# 04_LCD.net
KiCad netlist of a schematic drawn in Altium Designer
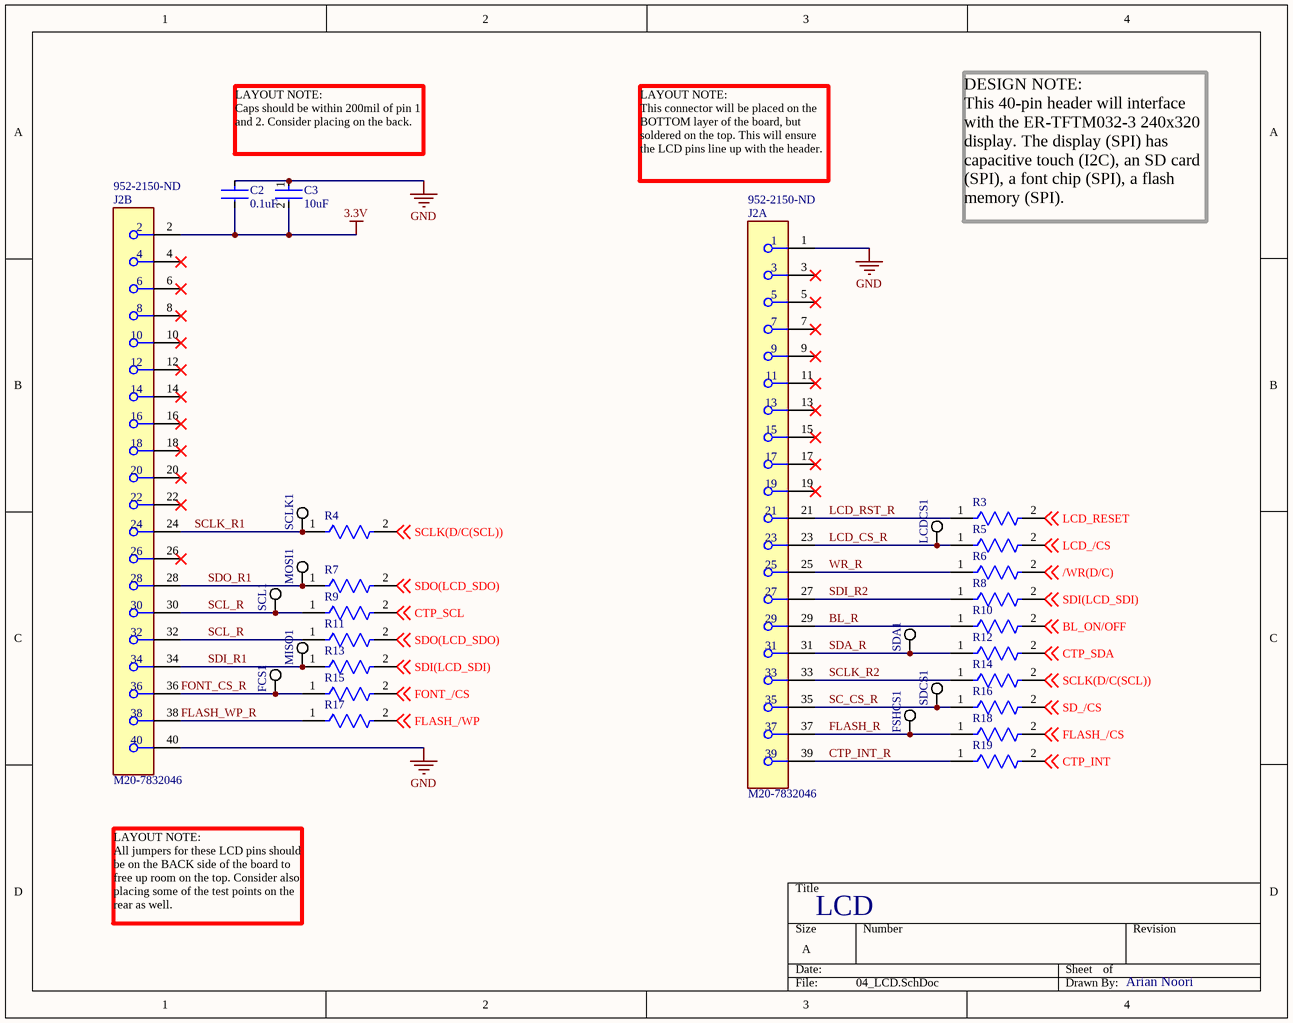
[diagram p0: 04_LCD.SchDoc]

(export (version "E")
  (design (tool "Eeschema 10.0.6"))
  (components
    (comp (ref "C2")
      (value "0.1uF")
      (footprint "FP-CL21-IPC_C")
      (description "CL21 Series 0805 100nF 50V ±10% Tolerance X7R Multilayer Ceramic Chip Capacitor")
      (fields (field (name "TOLERANCE") "10%") (field (name "VOLTAGE") "50V"))
      (libsource (lib "Altium Content Vault") (part "b4654b650e69147ec39a6b967a45e02"))
    )
    (comp (ref "C3")
      (value "10uF")
      (footprint "FP-C0805C-DG-MFG")
      (description "CAP CER 10UF 10V X5R 0805")
      (fields (field (name "TOLERANCE") "10%") (field (name "MANUFACTURER PART NUMBER") "C0805C106K8PACTU"))
      (libsource (lib "Altium Content Vault") (part "11868f565c42a9108669ba33697ecf6"))
    )
    (comp (ref "FCS1")
      (value "5019")
      (footprint "KSTN-5019_V")
      (description "Test Point, 1 Position SMD, RoHS, Tape and Reel")
      (fields (field (name "MANUFACTURER") "Keystone Electronics"))
      (libsource (lib "Altium Content Vault") (part "TESTPOINT_WHITE"))
    )
    (comp (ref "FSHCS1")
      (value "5019")
      (footprint "KSTN-5019_V")
      (description "Test Point, 1 Position SMD, RoHS, Tape and Reel")
      (fields (field (name "MANUFACTURER") "Keystone Electronics"))
      (libsource (lib "Altium Content Vault") (part "TESTPOINT_WHITE"))
    )
    (comp (ref "J2")
      (value "M20-7832046")
      (footprint "FP-M20-7832046-MFG")
      (description "CONN RCPT 40POS 0.1 TIN PCB")
      (fields (field (name "SUPPLIER PART NUMBER 1") "952-2150-ND") (field (name "MANUFACTURER") "Harwin"))
      (libsource (lib "Altium Content Vault") (part "e49c40d8a4b72700ef4f9e86232dadc"))
    )
    (comp (ref "LCDCS1")
      (value "5019")
      (footprint "KSTN-5019_V")
      (description "Test Point, 1 Position SMD, RoHS, Tape and Reel")
      (fields (field (name "MANUFACTURER") "Keystone Electronics"))
      (libsource (lib "Altium Content Vault") (part "TESTPOINT_WHITE"))
    )
    (comp (ref "MISO1")
      (value "5019")
      (footprint "KSTN-5019_V")
      (description "Test Point, 1 Position SMD, RoHS, Tape and Reel")
      (fields (field (name "MANUFACTURER") "Keystone Electronics"))
      (libsource (lib "Altium Content Vault") (part "TESTPOINT_WHITE"))
    )
    (comp (ref "MOSI1")
      (value "5019")
      (footprint "KSTN-5019_V")
      (description "Test Point, 1 Position SMD, RoHS, Tape and Reel")
      (fields (field (name "MANUFACTURER") "Keystone Electronics"))
      (libsource (lib "Altium Content Vault") (part "TESTPOINT_WHITE"))
    )
    (comp (ref "R3")
      (value "~")
      (footprint "FP-RC0805-MFG")
      (description "RES SMD 0 OHM JUMPER 1/8W 0805")
      (fields
        (field (name "OCTOPART") "https://octopart.com/rc0805fr-070rl-yageo-9293404")
        (field (name "MANUFACTURER") "Yageo")
      )
      (libsource (lib "Altium Content Vault") (part "1029c3af85768c4190bb7ad29bc67b5"))
    )
    (comp (ref "R4")
      (value "~")
      (footprint "FP-RC0805-MFG")
      (description "RES SMD 0 OHM JUMPER 1/8W 0805")
      (fields
        (field (name "OCTOPART") "https://octopart.com/rc0805fr-070rl-yageo-9293404")
        (field (name "MANUFACTURER") "Yageo")
      )
      (libsource (lib "Altium Content Vault") (part "1029c3af85768c4190bb7ad29bc67b5"))
    )
    (comp (ref "R5")
      (value "~")
      (footprint "FP-RC0805-MFG")
      (description "RES SMD 0 OHM JUMPER 1/8W 0805")
      (fields
        (field (name "OCTOPART") "https://octopart.com/rc0805fr-070rl-yageo-9293404")
        (field (name "MANUFACTURER") "Yageo")
      )
      (libsource (lib "Altium Content Vault") (part "1029c3af85768c4190bb7ad29bc67b5"))
    )
    (comp (ref "R6")
      (value "~")
      (footprint "FP-RC0805-MFG")
      (description "RES SMD 0 OHM JUMPER 1/8W 0805")
      (fields
        (field (name "OCTOPART") "https://octopart.com/rc0805fr-070rl-yageo-9293404")
        (field (name "MANUFACTURER") "Yageo")
      )
      (libsource (lib "Altium Content Vault") (part "1029c3af85768c4190bb7ad29bc67b5"))
    )
    (comp (ref "R7")
      (value "~")
      (footprint "FP-RC0805-MFG")
      (description "RES SMD 0 OHM JUMPER 1/8W 0805")
      (fields
        (field (name "OCTOPART") "https://octopart.com/rc0805fr-070rl-yageo-9293404")
        (field (name "MANUFACTURER") "Yageo")
      )
      (libsource (lib "Altium Content Vault") (part "1029c3af85768c4190bb7ad29bc67b5"))
    )
    (comp (ref "R8")
      (value "~")
      (footprint "FP-RC0805-MFG")
      (description "RES SMD 0 OHM JUMPER 1/8W 0805")
      (fields
        (field (name "OCTOPART") "https://octopart.com/rc0805fr-070rl-yageo-9293404")
        (field (name "MANUFACTURER") "Yageo")
      )
      (libsource (lib "Altium Content Vault") (part "1029c3af85768c4190bb7ad29bc67b5"))
    )
    (comp (ref "R9")
      (value "~")
      (footprint "FP-RC0805-MFG")
      (description "RES SMD 0 OHM JUMPER 1/8W 0805")
      (fields
        (field (name "OCTOPART") "https://octopart.com/rc0805fr-070rl-yageo-9293404")
        (field (name "MANUFACTURER") "Yageo")
      )
      (libsource (lib "Altium Content Vault") (part "1029c3af85768c4190bb7ad29bc67b5"))
    )
    (comp (ref "R10")
      (value "~")
      (footprint "FP-RC0805-MFG")
      (description "RES SMD 0 OHM JUMPER 1/8W 0805")
      (fields
        (field (name "OCTOPART") "https://octopart.com/rc0805fr-070rl-yageo-9293404")
        (field (name "MANUFACTURER") "Yageo")
      )
      (libsource (lib "Altium Content Vault") (part "1029c3af85768c4190bb7ad29bc67b5"))
    )
    (comp (ref "R11")
      (value "~")
      (footprint "FP-RC0805-MFG")
      (description "RES SMD 0 OHM JUMPER 1/8W 0805")
      (fields
        (field (name "OCTOPART") "https://octopart.com/rc0805fr-070rl-yageo-9293404")
        (field (name "MANUFACTURER") "Yageo")
      )
      (libsource (lib "Altium Content Vault") (part "1029c3af85768c4190bb7ad29bc67b5"))
    )
    (comp (ref "R12")
      (value "~")
      (footprint "FP-RC0805-MFG")
      (description "RES SMD 0 OHM JUMPER 1/8W 0805")
      (fields
        (field (name "OCTOPART") "https://octopart.com/rc0805fr-070rl-yageo-9293404")
        (field (name "MANUFACTURER") "Yageo")
      )
      (libsource (lib "Altium Content Vault") (part "1029c3af85768c4190bb7ad29bc67b5"))
    )
    (comp (ref "R13")
      (value "~")
      (footprint "FP-RC0805-MFG")
      (description "RES SMD 0 OHM JUMPER 1/8W 0805")
      (fields
        (field (name "OCTOPART") "https://octopart.com/rc0805fr-070rl-yageo-9293404")
        (field (name "MANUFACTURER") "Yageo")
      )
      (libsource (lib "Altium Content Vault") (part "1029c3af85768c4190bb7ad29bc67b5"))
    )
    (comp (ref "R14")
      (value "~")
      (footprint "FP-RC0805-MFG")
      (description "RES SMD 0 OHM JUMPER 1/8W 0805")
      (fields
        (field (name "OCTOPART") "https://octopart.com/rc0805fr-070rl-yageo-9293404")
        (field (name "MANUFACTURER") "Yageo")
      )
      (libsource (lib "Altium Content Vault") (part "1029c3af85768c4190bb7ad29bc67b5"))
    )
    (comp (ref "R15")
      (value "~")
      (footprint "FP-RC0805-MFG")
      (description "RES SMD 0 OHM JUMPER 1/8W 0805")
      (fields
        (field (name "OCTOPART") "https://octopart.com/rc0805fr-070rl-yageo-9293404")
        (field (name "MANUFACTURER") "Yageo")
      )
      (libsource (lib "Altium Content Vault") (part "1029c3af85768c4190bb7ad29bc67b5"))
    )
    (comp (ref "R16")
      (value "~")
      (footprint "FP-RC0805-MFG")
      (description "RES SMD 0 OHM JUMPER 1/8W 0805")
      (fields
        (field (name "OCTOPART") "https://octopart.com/rc0805fr-070rl-yageo-9293404")
        (field (name "MANUFACTURER") "Yageo")
      )
      (libsource (lib "Altium Content Vault") (part "1029c3af85768c4190bb7ad29bc67b5"))
    )
    (comp (ref "R17")
      (value "~")
      (footprint "FP-RC0805-MFG")
      (description "RES SMD 0 OHM JUMPER 1/8W 0805")
      (fields
        (field (name "OCTOPART") "https://octopart.com/rc0805fr-070rl-yageo-9293404")
        (field (name "MANUFACTURER") "Yageo")
      )
      (libsource (lib "Altium Content Vault") (part "1029c3af85768c4190bb7ad29bc67b5"))
    )
    (comp (ref "R18")
      (value "~")
      (footprint "FP-RC0805-MFG")
      (description "RES SMD 0 OHM JUMPER 1/8W 0805")
      (fields
        (field (name "OCTOPART") "https://octopart.com/rc0805fr-070rl-yageo-9293404")
        (field (name "MANUFACTURER") "Yageo")
      )
      (libsource (lib "Altium Content Vault") (part "1029c3af85768c4190bb7ad29bc67b5"))
    )
    (comp (ref "R19")
      (value "~")
      (footprint "FP-RC0805-MFG")
      (description "RES SMD 0 OHM JUMPER 1/8W 0805")
      (fields
        (field (name "OCTOPART") "https://octopart.com/rc0805fr-070rl-yageo-9293404")
        (field (name "MANUFACTURER") "Yageo")
      )
      (libsource (lib "Altium Content Vault") (part "1029c3af85768c4190bb7ad29bc67b5"))
    )
    (comp (ref "SCL1")
      (value "5019")
      (footprint "KSTN-5019_V")
      (description "Test Point, 1 Position SMD, RoHS, Tape and Reel")
      (fields (field (name "MANUFACTURER") "Keystone Electronics"))
      (libsource (lib "Altium Content Vault") (part "TESTPOINT_WHITE"))
    )
    (comp (ref "SCLK1")
      (value "5019")
      (footprint "KSTN-5019_V")
      (description "Test Point, 1 Position SMD, RoHS, Tape and Reel")
      (fields (field (name "MANUFACTURER") "Keystone Electronics"))
      (libsource (lib "Altium Content Vault") (part "TESTPOINT_WHITE"))
    )
    (comp (ref "SDA1")
      (value "5019")
      (footprint "KSTN-5019_V")
      (description "Test Point, 1 Position SMD, RoHS, Tape and Reel")
      (fields (field (name "MANUFACTURER") "Keystone Electronics"))
      (libsource (lib "Altium Content Vault") (part "TESTPOINT_WHITE"))
    )
    (comp (ref "SDCS1")
      (value "5019")
      (footprint "KSTN-5019_V")
      (description "Test Point, 1 Position SMD, RoHS, Tape and Reel")
      (fields (field (name "MANUFACTURER") "Keystone Electronics"))
      (libsource (lib "Altium Content Vault") (part "TESTPOINT_WHITE"))
    )
  )
  (nets
    (net (code "1") (name "/BL_R") (class "Default")
      (node (ref "J2") (pin "29") (pinfunction "29_29") (pintype "passive"))
      (node (ref "R10") (pin "1") (pinfunction "1_1") (pintype "passive"))
    )
    (net (code "2") (name "/CTP_INT_R") (class "Default")
      (node (ref "J2") (pin "39") (pinfunction "39_39") (pintype "passive"))
      (node (ref "R19") (pin "1") (pinfunction "1_1") (pintype "passive"))
    )
    (net (code "3") (name "/FLASH_R") (class "Default")
      (node (ref "FSHCS1") (pin "1") (pinfunction "1_1") (pintype "passive"))
      (node (ref "J2") (pin "37") (pinfunction "37_37") (pintype "passive"))
      (node (ref "R18") (pin "1") (pinfunction "1_1") (pintype "passive"))
    )
    (net (code "4") (name "/FLASH_WP_R") (class "Default")
      (node (ref "J2") (pin "38") (pinfunction "38_38") (pintype "passive"))
      (node (ref "R17") (pin "1") (pinfunction "1_1") (pintype "passive"))
    )
    (net (code "5") (name "/FONT_CS_R") (class "Default")
      (node (ref "FCS1") (pin "1") (pinfunction "1_1") (pintype "passive"))
      (node (ref "J2") (pin "36") (pinfunction "36_36") (pintype "passive"))
      (node (ref "R15") (pin "1") (pinfunction "1_1") (pintype "passive"))
    )
    (net (code "6") (name "/LCD_CS_R") (class "Default")
      (node (ref "J2") (pin "23") (pinfunction "23_23") (pintype "passive"))
      (node (ref "LCDCS1") (pin "1") (pinfunction "1_1") (pintype "passive"))
      (node (ref "R5") (pin "1") (pinfunction "1_1") (pintype "passive"))
    )
    (net (code "7") (name "/LCD_RST_R") (class "Default")
      (node (ref "J2") (pin "21") (pinfunction "21_21") (pintype "passive"))
      (node (ref "R3") (pin "1") (pinfunction "1_1") (pintype "passive"))
    )
    (net (code "8") (name "/SCLK_R1") (class "Default")
      (node (ref "J2") (pin "24") (pinfunction "24_24") (pintype "passive"))
      (node (ref "R4") (pin "1") (pinfunction "1_1") (pintype "passive"))
      (node (ref "SCLK1") (pin "1") (pinfunction "1_1") (pintype "passive"))
    )
    (net (code "9") (name "/SCLK_R2") (class "Default")
      (node (ref "J2") (pin "33") (pinfunction "33_33") (pintype "passive"))
      (node (ref "R14") (pin "1") (pinfunction "1_1") (pintype "passive"))
    )
    (net (code "10") (name "/SCL_R") (class "Default")
      (node (ref "J2") (pin "30") (pinfunction "30_30") (pintype "passive"))
      (node (ref "J2") (pin "32") (pinfunction "32_32") (pintype "passive"))
      (node (ref "R11") (pin "1") (pinfunction "1_1") (pintype "passive"))
      (node (ref "R9") (pin "1") (pinfunction "1_1") (pintype "passive"))
      (node (ref "SCL1") (pin "1") (pinfunction "1_1") (pintype "passive"))
    )
    (net (code "11") (name "/SC_CS_R") (class "Default")
      (node (ref "J2") (pin "35") (pinfunction "35_35") (pintype "passive"))
      (node (ref "R16") (pin "1") (pinfunction "1_1") (pintype "passive"))
      (node (ref "SDCS1") (pin "1") (pinfunction "1_1") (pintype "passive"))
    )
    (net (code "12") (name "/SDA_R") (class "Default")
      (node (ref "J2") (pin "31") (pinfunction "31_31") (pintype "passive"))
      (node (ref "R12") (pin "1") (pinfunction "1_1") (pintype "passive"))
      (node (ref "SDA1") (pin "1") (pinfunction "1_1") (pintype "passive"))
    )
    (net (code "13") (name "/SDI_R1") (class "Default")
      (node (ref "J2") (pin "34") (pinfunction "34_34") (pintype "passive"))
      (node (ref "MISO1") (pin "1") (pinfunction "1_1") (pintype "passive"))
      (node (ref "R13") (pin "1") (pinfunction "1_1") (pintype "passive"))
    )
    (net (code "14") (name "/SDI_R2") (class "Default")
      (node (ref "J2") (pin "27") (pinfunction "27_27") (pintype "passive"))
      (node (ref "R8") (pin "1") (pinfunction "1_1") (pintype "passive"))
    )
    (net (code "15") (name "/SDO_R1") (class "Default")
      (node (ref "J2") (pin "28") (pinfunction "28_28") (pintype "passive"))
      (node (ref "MOSI1") (pin "1") (pinfunction "1_1") (pintype "passive"))
      (node (ref "R7") (pin "1") (pinfunction "1_1") (pintype "passive"))
    )
    (net (code "16") (name "/WR_R") (class "Default")
      (node (ref "J2") (pin "25") (pinfunction "25_25") (pintype "passive"))
      (node (ref "R6") (pin "1") (pinfunction "1_1") (pintype "passive"))
    )
    (net (code "17") (name "3.3V") (class "Default")
      (node (ref "C2") (pin "2") (pinfunction "2_2") (pintype "passive"))
      (node (ref "C3") (pin "2") (pinfunction "2_2") (pintype "passive"))
      (node (ref "J2") (pin "2") (pinfunction "2_2") (pintype "passive"))
    )
    (net (code "18") (name "BL_ON{slash}OFF") (class "Default")
      (node (ref "R10") (pin "2") (pinfunction "2_2") (pintype "passive"))
    )
    (net (code "19") (name "CTP_INT") (class "Default")
      (node (ref "R19") (pin "2") (pinfunction "2_2") (pintype "passive"))
    )
    (net (code "20") (name "CTP_SCL") (class "Default")
      (node (ref "R9") (pin "2") (pinfunction "2_2") (pintype "passive"))
    )
    (net (code "21") (name "CTP_SDA") (class "Default")
      (node (ref "R12") (pin "2") (pinfunction "2_2") (pintype "passive"))
    )
    (net (code "22") (name "FLASH_{slash}CS") (class "Default")
      (node (ref "R18") (pin "2") (pinfunction "2_2") (pintype "passive"))
    )
    (net (code "23") (name "FLASH_{slash}WP") (class "Default")
      (node (ref "R17") (pin "2") (pinfunction "2_2") (pintype "passive"))
    )
    (net (code "24") (name "FONT_{slash}CS") (class "Default")
      (node (ref "R15") (pin "2") (pinfunction "2_2") (pintype "passive"))
    )
    (net (code "25") (name "GND") (class "Default")
      (node (ref "C2") (pin "1") (pinfunction "1_1") (pintype "passive"))
      (node (ref "C3") (pin "1") (pinfunction "1_1") (pintype "passive"))
      (node (ref "J2") (pin "1") (pinfunction "1_1") (pintype "passive"))
      (node (ref "J2") (pin "40") (pinfunction "40_40") (pintype "passive"))
    )
    (net (code "26") (name "LCD_RESET") (class "Default")
      (node (ref "R3") (pin "2") (pinfunction "2_2") (pintype "passive"))
    )
    (net (code "27") (name "LCD_{slash}CS") (class "Default")
      (node (ref "R5") (pin "2") (pinfunction "2_2") (pintype "passive"))
    )
    (net (code "28") (name "SCLK(D{slash}C(SCL))") (class "Default")
      (node (ref "R14") (pin "2") (pinfunction "2_2") (pintype "passive"))
      (node (ref "R4") (pin "2") (pinfunction "2_2") (pintype "passive"))
    )
    (net (code "29") (name "SDI(LCD_SDI)") (class "Default")
      (node (ref "R13") (pin "2") (pinfunction "2_2") (pintype "passive"))
      (node (ref "R8") (pin "2") (pinfunction "2_2") (pintype "passive"))
    )
    (net (code "30") (name "SDO(LCD_SDO)") (class "Default")
      (node (ref "R11") (pin "2") (pinfunction "2_2") (pintype "passive"))
      (node (ref "R7") (pin "2") (pinfunction "2_2") (pintype "passive"))
    )
    (net (code "31") (name "SD_{slash}CS") (class "Default")
      (node (ref "R16") (pin "2") (pinfunction "2_2") (pintype "passive"))
    )
    (net (code "32") (name "unconnected-(J2-Pad3)") (class "Default")
      (node (ref "J2") (pin "3") (pinfunction "3_3") (pintype "passive+no_connect"))
    )
    (net (code "33") (name "unconnected-(J2-Pad4)") (class "Default")
      (node (ref "J2") (pin "4") (pinfunction "4_4") (pintype "passive+no_connect"))
    )
    (net (code "34") (name "unconnected-(J2-Pad5)") (class "Default")
      (node (ref "J2") (pin "5") (pinfunction "5_5") (pintype "passive+no_connect"))
    )
    (net (code "35") (name "unconnected-(J2-Pad6)") (class "Default")
      (node (ref "J2") (pin "6") (pinfunction "6_6") (pintype "passive+no_connect"))
    )
    (net (code "36") (name "unconnected-(J2-Pad7)") (class "Default")
      (node (ref "J2") (pin "7") (pinfunction "7_7") (pintype "passive+no_connect"))
    )
    (net (code "37") (name "unconnected-(J2-Pad8)") (class "Default")
      (node (ref "J2") (pin "8") (pinfunction "8_8") (pintype "passive+no_connect"))
    )
    (net (code "38") (name "unconnected-(J2-Pad9)") (class "Default")
      (node (ref "J2") (pin "9") (pinfunction "9_9") (pintype "passive+no_connect"))
    )
    (net (code "39") (name "unconnected-(J2-Pad10)") (class "Default")
      (node (ref "J2") (pin "10") (pinfunction "10_10") (pintype "passive+no_connect"))
    )
    (net (code "40") (name "unconnected-(J2-Pad11)") (class "Default")
      (node (ref "J2") (pin "11") (pinfunction "11_11") (pintype "passive+no_connect"))
    )
    (net (code "41") (name "unconnected-(J2-Pad12)") (class "Default")
      (node (ref "J2") (pin "12") (pinfunction "12_12") (pintype "passive+no_connect"))
    )
    (net (code "42") (name "unconnected-(J2-Pad13)") (class "Default")
      (node (ref "J2") (pin "13") (pinfunction "13_13") (pintype "passive+no_connect"))
    )
    (net (code "43") (name "unconnected-(J2-Pad14)") (class "Default")
      (node (ref "J2") (pin "14") (pinfunction "14_14") (pintype "passive+no_connect"))
    )
    (net (code "44") (name "unconnected-(J2-Pad15)") (class "Default")
      (node (ref "J2") (pin "15") (pinfunction "15_15") (pintype "passive+no_connect"))
    )
    (net (code "45") (name "unconnected-(J2-Pad16)") (class "Default")
      (node (ref "J2") (pin "16") (pinfunction "16_16") (pintype "passive+no_connect"))
    )
    (net (code "46") (name "unconnected-(J2-Pad17)") (class "Default")
      (node (ref "J2") (pin "17") (pinfunction "17_17") (pintype "passive+no_connect"))
    )
    (net (code "47") (name "unconnected-(J2-Pad18)") (class "Default")
      (node (ref "J2") (pin "18") (pinfunction "18_18") (pintype "passive+no_connect"))
    )
    (net (code "48") (name "unconnected-(J2-Pad19)") (class "Default")
      (node (ref "J2") (pin "19") (pinfunction "19_19") (pintype "passive+no_connect"))
    )
    (net (code "49") (name "unconnected-(J2-Pad20)") (class "Default")
      (node (ref "J2") (pin "20") (pinfunction "20_20") (pintype "passive+no_connect"))
    )
    (net (code "50") (name "unconnected-(J2-Pad22)") (class "Default")
      (node (ref "J2") (pin "22") (pinfunction "22_22") (pintype "passive+no_connect"))
    )
    (net (code "51") (name "unconnected-(J2-Pad26)") (class "Default")
      (node (ref "J2") (pin "26") (pinfunction "26_26") (pintype "passive+no_connect"))
    )
    (net (code "52") (name "{slash}WR(D{slash}C)") (class "Default")
      (node (ref "R6") (pin "2") (pinfunction "2_2") (pintype "passive"))
    )
  )
)
